# ID_PCB.net
KiCad netlist of a schematic drawn in EasyEDA Pro
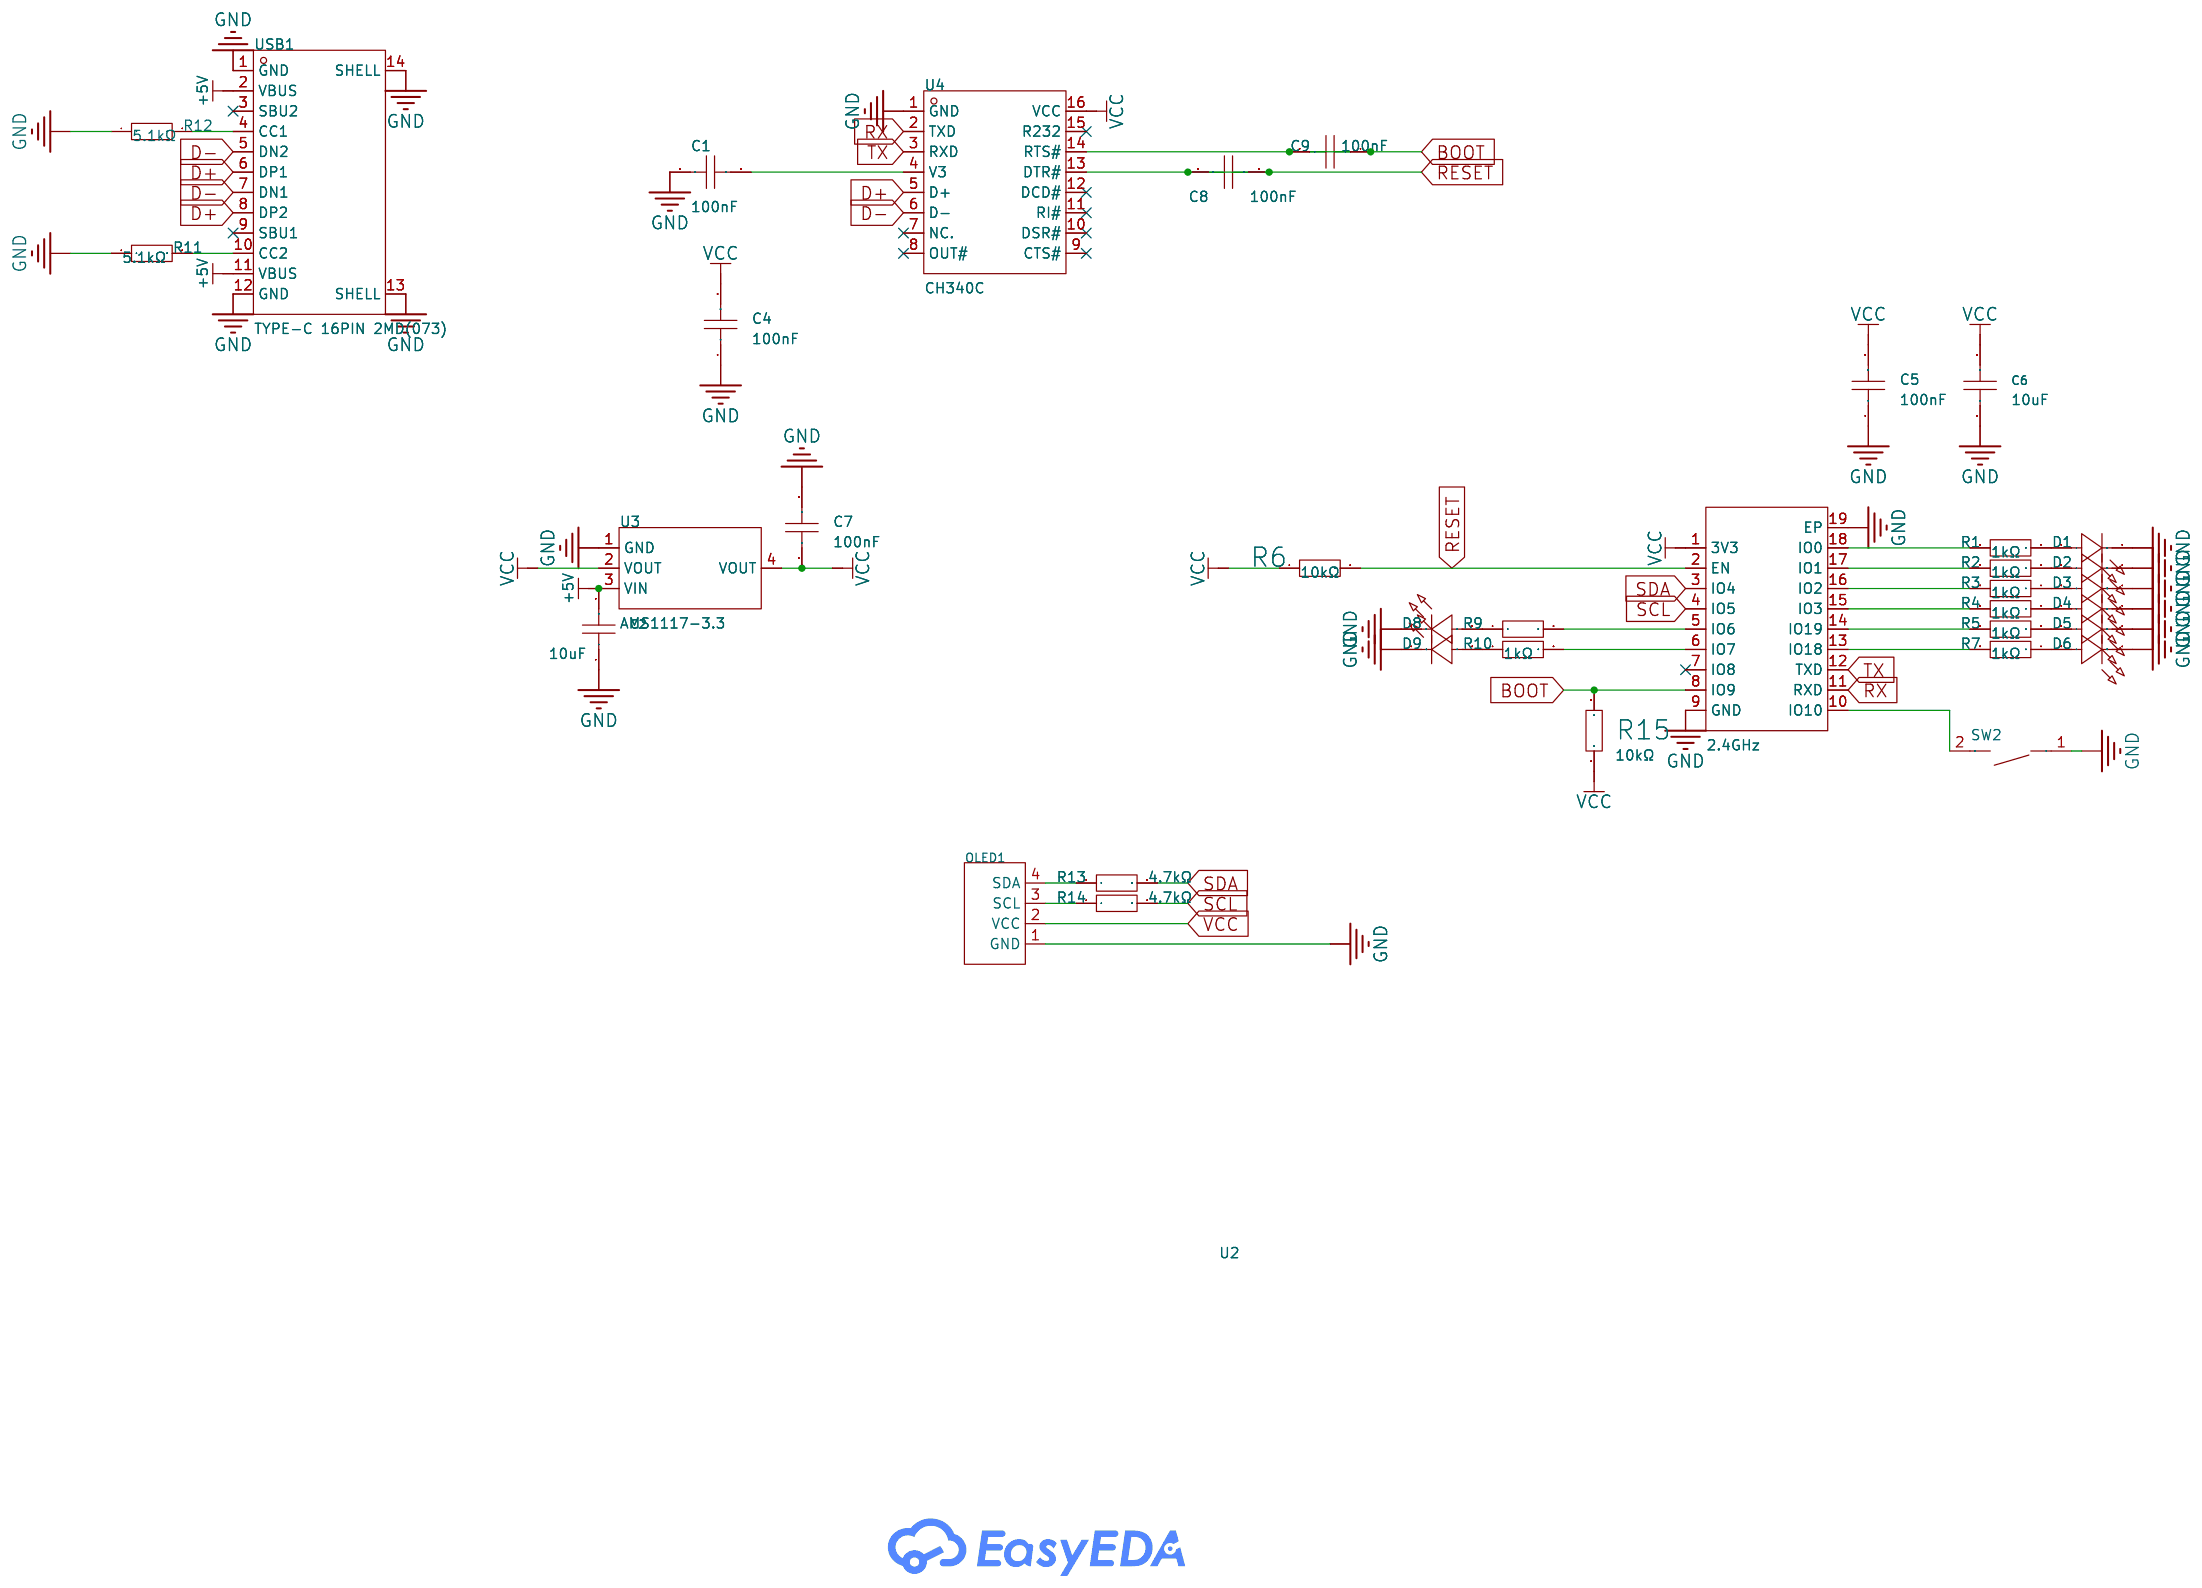
[diagram p0: schematic sheet]

(export (version "E")
  (design (tool "Eeschema 10.0.6"))
  (components
    (comp (ref "C1")
      (value "100nF")
      (footprint "easyedapro:C0603")
      (description "Capacitance:100nF Tolerance:±10% Tolerance:±10% Voltage Rating:50V Temperature Coefficient:X7R")
      (fields
        (field (name "Manufacturer Part") "CC0603KRX7R9BB104")
        (field (name "Manufacturer") "YAGEO(国巨)")
      )
      (libsource (lib "easyedapro") (part "CC0603KRX7R9BB104"))
    )
    (comp (ref "C2")
      (value "10uF")
      (footprint "easyedapro:C0603")
      (description "Capacitance:10uF Tolerance:±20% Tolerance:±20% Voltage Rating:25V Temperature Coefficient:X5R")
      (fields
        (field (name "Manufacturer Part") "CL10A106MA8NRNC")
        (field (name "Manufacturer") "SAMSUNG(三星)")
      )
      (libsource (lib "easyedapro") (part "CL10A106MA8NRNC"))
    )
    (comp (ref "C4")
      (value "100nF")
      (footprint "easyedapro:C0603")
      (description "Capacitance:100nF Tolerance:±10% Tolerance:±10% Voltage Rating:50V Temperature Coefficient:X7R")
      (fields
        (field (name "Manufacturer Part") "CC0603KRX7R9BB104")
        (field (name "Manufacturer") "YAGEO(国巨)")
      )
      (libsource (lib "easyedapro") (part "CC0603KRX7R9BB104"))
    )
    (comp (ref "C5")
      (value "100nF")
      (footprint "easyedapro:C0603")
      (description "Capacitance:100nF Tolerance:±10% Tolerance:±10% Voltage Rating:50V Temperature Coefficient:X7R")
      (fields
        (field (name "Manufacturer Part") "CC0603KRX7R9BB104")
        (field (name "Manufacturer") "YAGEO(国巨)")
      )
      (libsource (lib "easyedapro") (part "CC0603KRX7R9BB104"))
    )
    (comp (ref "C6")
      (value "10uF")
      (footprint "easyedapro:C0603")
      (description "Capacitance:10uF Tolerance:±20% Tolerance:±20% Voltage Rating:25V Temperature Coefficient:X5R")
      (fields
        (field (name "Manufacturer Part") "CL10A106MA8NRNC")
        (field (name "Manufacturer") "SAMSUNG(三星)")
      )
      (libsource (lib "easyedapro") (part "CL10A106MA8NRNC"))
    )
    (comp (ref "C7")
      (value "100nF")
      (footprint "easyedapro:C0603")
      (description "Capacitance:100nF Tolerance:±10% Tolerance:±10% Voltage Rating:50V Temperature Coefficient:X7R")
      (fields
        (field (name "Manufacturer Part") "CC0603KRX7R9BB104")
        (field (name "Manufacturer") "YAGEO(国巨)")
      )
      (libsource (lib "easyedapro") (part "CC0603KRX7R9BB104"))
    )
    (comp (ref "C8")
      (value "100nF")
      (footprint "easyedapro:C0603")
      (description "Capacitance:100nF Tolerance:±10% Tolerance:±10% Voltage Rating:50V Temperature Coefficient:X7R")
      (fields
        (field (name "Manufacturer Part") "CC0603KRX7R9BB104")
        (field (name "Manufacturer") "YAGEO(国巨)")
      )
      (libsource (lib "easyedapro") (part "CC0603KRX7R9BB104"))
    )
    (comp (ref "C9")
      (value "100nF")
      (footprint "easyedapro:C0603")
      (description "Capacitance:100nF Tolerance:±10% Tolerance:±10% Voltage Rating:50V Temperature Coefficient:X7R")
      (fields
        (field (name "Manufacturer Part") "CC0603KRX7R9BB104")
        (field (name "Manufacturer") "YAGEO(国巨)")
      )
      (libsource (lib "easyedapro") (part "CC0603KRX7R9BB104"))
    )
    (comp (ref "D1")
      (value "YLED0603Y")
      (footprint "easyedapro:LED0603-RD-1")
      (fields (field (name "Manufacturer") "YONGYUTAI(永裕泰)"))
      (libsource (lib "easyedapro") (part "YLED0603Y"))
    )
    (comp (ref "D2")
      (value "YLED0603Y")
      (footprint "easyedapro:LED0603-RD-1")
      (fields (field (name "Manufacturer") "YONGYUTAI(永裕泰)"))
      (libsource (lib "easyedapro") (part "YLED0603Y"))
    )
    (comp (ref "D3")
      (value "YLED0603Y")
      (footprint "easyedapro:LED0603-RD-1")
      (fields (field (name "Manufacturer") "YONGYUTAI(永裕泰)"))
      (libsource (lib "easyedapro") (part "YLED0603Y"))
    )
    (comp (ref "D4")
      (value "YLED0603Y")
      (footprint "easyedapro:LED0603-RD-1")
      (fields (field (name "Manufacturer") "YONGYUTAI(永裕泰)"))
      (libsource (lib "easyedapro") (part "YLED0603Y"))
    )
    (comp (ref "D5")
      (value "YLED0603Y")
      (footprint "easyedapro:LED0603-RD-1")
      (fields (field (name "Manufacturer") "YONGYUTAI(永裕泰)"))
      (libsource (lib "easyedapro") (part "YLED0603Y"))
    )
    (comp (ref "D6")
      (value "YLED0603Y")
      (footprint "easyedapro:LED0603-RD-1")
      (fields (field (name "Manufacturer") "YONGYUTAI(永裕泰)"))
      (libsource (lib "easyedapro") (part "YLED0603Y"))
    )
    (comp (ref "D8")
      (value "YLED0603Y")
      (footprint "easyedapro:LED0603-RD-1")
      (fields (field (name "Manufacturer") "YONGYUTAI(永裕泰)"))
      (libsource (lib "easyedapro") (part "YLED0603Y"))
    )
    (comp (ref "D9")
      (value "YLED0603Y")
      (footprint "easyedapro:LED0603-RD-1")
      (fields (field (name "Manufacturer") "YONGYUTAI(永裕泰)"))
      (libsource (lib "easyedapro") (part "YLED0603Y"))
    )
    (comp (ref "OLED1")
      (value "HS91L02W2C01")
      (footprint "easyedapro:OLED-TH_L38.0-W12.0_HS91L02W2C01")
      (fields (field (name "Manufacturer") "HS(汉昇)"))
      (libsource (lib "easyedapro") (part "HS91L02W2C01"))
    )
    (comp (ref "R1")
      (value "1kΩ")
      (footprint "easyedapro:R0603")
      (fields
        (field (name "Manufacturer Part") "0603WAF1001T5E")
        (field (name "Manufacturer") "UNI-ROYAL(厚声)")
      )
      (libsource (lib "easyedapro") (part "0603WAF1001T5E"))
    )
    (comp (ref "R2")
      (value "1kΩ")
      (footprint "easyedapro:R0603")
      (fields
        (field (name "Manufacturer Part") "0603WAF1001T5E")
        (field (name "Manufacturer") "UNI-ROYAL(厚声)")
      )
      (libsource (lib "easyedapro") (part "0603WAF1001T5E"))
    )
    (comp (ref "R3")
      (value "1kΩ")
      (footprint "easyedapro:R0603")
      (fields
        (field (name "Manufacturer Part") "0603WAF1001T5E")
        (field (name "Manufacturer") "UNI-ROYAL(厚声)")
      )
      (libsource (lib "easyedapro") (part "0603WAF1001T5E"))
    )
    (comp (ref "R4")
      (value "1kΩ")
      (footprint "easyedapro:R0603")
      (fields
        (field (name "Manufacturer Part") "0603WAF1001T5E")
        (field (name "Manufacturer") "UNI-ROYAL(厚声)")
      )
      (libsource (lib "easyedapro") (part "0603WAF1001T5E"))
    )
    (comp (ref "R5")
      (value "1kΩ")
      (footprint "easyedapro:R0603")
      (fields
        (field (name "Manufacturer Part") "0603WAF1001T5E")
        (field (name "Manufacturer") "UNI-ROYAL(厚声)")
      )
      (libsource (lib "easyedapro") (part "0603WAF1001T5E"))
    )
    (comp (ref "R6")
      (value "10kΩ")
      (footprint "easyedapro:R0603")
      (fields
        (field (name "Manufacturer Part") "0603WAF1002T5E")
        (field (name "Manufacturer") "UNI-ROYAL(厚声)")
      )
      (libsource (lib "easyedapro") (part "0603WAF1002T5E"))
    )
    (comp (ref "R7")
      (value "1kΩ")
      (footprint "easyedapro:R0603")
      (fields
        (field (name "Manufacturer Part") "0603WAF1001T5E")
        (field (name "Manufacturer") "UNI-ROYAL(厚声)")
      )
      (libsource (lib "easyedapro") (part "0603WAF1001T5E"))
    )
    (comp (ref "R9")
      (value "1kΩ")
      (footprint "easyedapro:R0603")
      (fields
        (field (name "Manufacturer Part") "0603WAF1001T5E")
        (field (name "Manufacturer") "UNI-ROYAL(厚声)")
      )
      (libsource (lib "easyedapro") (part "0603WAF1001T5E"))
    )
    (comp (ref "R10")
      (value "1kΩ")
      (footprint "easyedapro:R0603")
      (fields
        (field (name "Manufacturer Part") "0603WAF1001T5E")
        (field (name "Manufacturer") "UNI-ROYAL(厚声)")
      )
      (libsource (lib "easyedapro") (part "0603WAF1001T5E"))
    )
    (comp (ref "R11")
      (value "5.1kΩ")
      (footprint "easyedapro:R0603")
      (fields
        (field (name "Manufacturer Part") "0603WAF5101T5E")
        (field (name "Manufacturer") "UNI-ROYAL(厚声)")
      )
      (libsource (lib "easyedapro") (part "0603WAF5101T5E"))
    )
    (comp (ref "R12")
      (value "5.1kΩ")
      (footprint "easyedapro:R0603")
      (fields
        (field (name "Manufacturer Part") "0603WAF5101T5E")
        (field (name "Manufacturer") "UNI-ROYAL(厚声)")
      )
      (libsource (lib "easyedapro") (part "0603WAF5101T5E"))
    )
    (comp (ref "R13")
      (value "4.7kΩ")
      (footprint "easyedapro:R0603")
      (fields (field (name "Manufacturer Part") "RC0603FR-074K7L") (field (name "Manufacturer") "YAGEO(国巨)"))
      (libsource (lib "easyedapro") (part "RC0603FR-074K7L"))
    )
    (comp (ref "R14")
      (value "4.7kΩ")
      (footprint "easyedapro:R0603")
      (fields (field (name "Manufacturer Part") "RC0603FR-074K7L") (field (name "Manufacturer") "YAGEO(国巨)"))
      (libsource (lib "easyedapro") (part "RC0603FR-074K7L"))
    )
    (comp (ref "R15")
      (value "10kΩ")
      (footprint "easyedapro:R0603")
      (fields
        (field (name "Manufacturer Part") "0603WAF1002T5E")
        (field (name "Manufacturer") "UNI-ROYAL(厚声)")
      )
      (libsource (lib "easyedapro") (part "0603WAF1002T5E"))
    )
    (comp (ref "SW2")
      (value "TS-1088-AR02016")
      (footprint "easyedapro:SW-SMD_L3.9-W3.0-P4.45")
      (fields (field (name "Manufacturer") "XUNPU(讯普)"))
      (libsource (lib "easyedapro") (part "TS-1088-AR02016"))
    )
    (comp (ref "U2")
      (value "2.4GHz")
      (footprint "easyedapro:BULETM-SMD_ESPRESSIF_ESP32-C3-WROOM-02-N4-4MB")
      (fields
        (field (name "Manufacturer Part") "ESP32-C3-WROOM-02-N4")
        (field (name "Manufacturer") "ESPRESSIF(乐鑫)")
      )
      (libsource (lib "easyedapro") (part "ESP32-C3-WROOM-02-N4(4MB)"))
    )
    (comp (ref "U3")
      (value "AMS1117-3.3")
      (footprint "easyedapro:SOT-223-3_L6.5-W3.4-P2.30-LS7.0-BR")
      (fields (field (name "Manufacturer") "AMS"))
      (libsource (lib "easyedapro") (part "AMS1117-3.3"))
    )
    (comp (ref "U4")
      (value "CH340C")
      (footprint "easyedapro:SOP-16_L10.0-W3.9-P1.27-LS6.0-BL")
      (fields (field (name "Manufacturer") "WCH(南京沁恒)"))
      (libsource (lib "easyedapro") (part "CH340C"))
    )
    (comp (ref "USB1")
      (value "TYPE-C 16PIN 2MD(073)")
      (footprint "easyedapro:USB-C-SMD_TYPE-C-6PIN-2MD-073")
      (fields (field (name "Manufacturer") "SHOU HAN(首韩)"))
      (libsource (lib "easyedapro") (part "TYPE-C 16PIN 2MD(073)"))
    )
  )
  (nets
    (net (code "1") (name "+5V") (class "Default")
      (node (ref "C2") (pin "2") (pinfunction "2_2") (pintype "input"))
      (node (ref "U3") (pin "3") (pinfunction "VIN_3") (pintype "unspecified"))
      (node (ref "USB1") (pin "11") (pinfunction "VBUS_11") (pintype "unspecified"))
      (node (ref "USB1") (pin "2") (pinfunction "VBUS_2") (pintype "unspecified"))
    )
    (net (code "2") (name "BOOT") (class "Default")
      (node (ref "C9") (pin "1") (pinfunction "1_1") (pintype "unspecified"))
      (node (ref "C9") (pin "2") (pinfunction "2_2") (pintype "unspecified"))
      (node (ref "R15") (pin "2") (pinfunction "2_2") (pintype "input"))
      (node (ref "U2") (pin "8") (pinfunction "IO9_8") (pintype "unspecified"))
      (node (ref "U4") (pin "14") (pinfunction "RTS#_14") (pintype "unspecified"))
    )
    (net (code "3") (name "D+") (class "Default")
      (node (ref "U4") (pin "5") (pinfunction "D+_5") (pintype "unspecified"))
      (node (ref "USB1") (pin "6") (pinfunction "DP1_6") (pintype "unspecified"))
      (node (ref "USB1") (pin "8") (pinfunction "DP2_8") (pintype "unspecified"))
    )
    (net (code "4") (name "D-") (class "Default")
      (node (ref "U4") (pin "6") (pinfunction "D-_6") (pintype "unspecified"))
      (node (ref "USB1") (pin "5") (pinfunction "DN2_5") (pintype "unspecified"))
      (node (ref "USB1") (pin "7") (pinfunction "DN1_7") (pintype "unspecified"))
    )
    (net (code "5") (name "GND") (class "Default")
      (node (ref "C1") (pin "1") (pinfunction "1_1") (pintype "unspecified"))
      (node (ref "C2") (pin "1") (pinfunction "1_1") (pintype "input"))
      (node (ref "C4") (pin "1") (pinfunction "1_1") (pintype "unspecified"))
      (node (ref "C5") (pin "1") (pinfunction "1_1") (pintype "unspecified"))
      (node (ref "C6") (pin "1") (pinfunction "1_1") (pintype "input"))
      (node (ref "C7") (pin "2") (pinfunction "2_2") (pintype "unspecified"))
      (node (ref "D1") (pin "1") (pinfunction "C_1") (pintype "unspecified"))
      (node (ref "D2") (pin "1") (pinfunction "C_1") (pintype "unspecified"))
      (node (ref "D3") (pin "1") (pinfunction "C_1") (pintype "unspecified"))
      (node (ref "D4") (pin "1") (pinfunction "C_1") (pintype "unspecified"))
      (node (ref "D5") (pin "1") (pinfunction "C_1") (pintype "unspecified"))
      (node (ref "D6") (pin "1") (pinfunction "C_1") (pintype "unspecified"))
      (node (ref "D8") (pin "1") (pinfunction "C_1") (pintype "unspecified"))
      (node (ref "D9") (pin "1") (pinfunction "C_1") (pintype "unspecified"))
      (node (ref "OLED1") (pin "1") (pinfunction "GND_1") (pintype "input"))
      (node (ref "R11") (pin "1") (pinfunction "1_1") (pintype "input"))
      (node (ref "R12") (pin "1") (pinfunction "1_1") (pintype "input"))
      (node (ref "SW2") (pin "1") (pinfunction "1_1") (pintype "unspecified"))
      (node (ref "U2") (pin "19") (pinfunction "EP_19") (pintype "unspecified"))
      (node (ref "U2") (pin "9") (pinfunction "GND_9") (pintype "unspecified"))
      (node (ref "U3") (pin "1") (pinfunction "GND_1") (pintype "unspecified"))
      (node (ref "U4") (pin "1") (pinfunction "GND_1") (pintype "unspecified"))
      (node (ref "USB1") (pin "1") (pinfunction "GND_1") (pintype "unspecified"))
      (node (ref "USB1") (pin "12") (pinfunction "GND_12") (pintype "unspecified"))
      (node (ref "USB1") (pin "13") (pinfunction "SHELL_13") (pintype "unspecified"))
      (node (ref "USB1") (pin "14") (pinfunction "SHELL_14") (pintype "unspecified"))
    )
    (net (code "6") (name "Net-(D1-A)") (class "Default")
      (node (ref "D1") (pin "2") (pinfunction "A_2") (pintype "unspecified"))
      (node (ref "R1") (pin "1") (pinfunction "1_1") (pintype "input"))
    )
    (net (code "7") (name "Net-(D2-A)") (class "Default")
      (node (ref "D2") (pin "2") (pinfunction "A_2") (pintype "unspecified"))
      (node (ref "R2") (pin "1") (pinfunction "1_1") (pintype "input"))
    )
    (net (code "8") (name "Net-(D3-A)") (class "Default")
      (node (ref "D3") (pin "2") (pinfunction "A_2") (pintype "unspecified"))
      (node (ref "R3") (pin "1") (pinfunction "1_1") (pintype "input"))
    )
    (net (code "9") (name "Net-(D4-A)") (class "Default")
      (node (ref "D4") (pin "2") (pinfunction "A_2") (pintype "unspecified"))
      (node (ref "R4") (pin "1") (pinfunction "1_1") (pintype "input"))
    )
    (net (code "10") (name "Net-(D5-A)") (class "Default")
      (node (ref "D5") (pin "2") (pinfunction "A_2") (pintype "unspecified"))
      (node (ref "R5") (pin "1") (pinfunction "1_1") (pintype "input"))
    )
    (net (code "11") (name "Net-(D6-A)") (class "Default")
      (node (ref "D6") (pin "2") (pinfunction "A_2") (pintype "unspecified"))
      (node (ref "R7") (pin "1") (pinfunction "1_1") (pintype "input"))
    )
    (net (code "12") (name "Net-(D8-A)") (class "Default")
      (node (ref "D8") (pin "2") (pinfunction "A_2") (pintype "unspecified"))
      (node (ref "R9") (pin "1") (pinfunction "1_1") (pintype "input"))
    )
    (net (code "13") (name "Net-(D9-A)") (class "Default")
      (node (ref "D9") (pin "2") (pinfunction "A_2") (pintype "unspecified"))
      (node (ref "R10") (pin "1") (pinfunction "1_1") (pintype "input"))
    )
    (net (code "14") (name "Net-(OLED1-SCL)") (class "Default")
      (node (ref "OLED1") (pin "3") (pinfunction "SCL_3") (pintype "input"))
      (node (ref "R14") (pin "1") (pinfunction "1_1") (pintype "input"))
    )
    (net (code "15") (name "Net-(OLED1-SDA)") (class "Default")
      (node (ref "OLED1") (pin "4") (pinfunction "SDA_4") (pintype "input"))
      (node (ref "R13") (pin "1") (pinfunction "1_1") (pintype "input"))
    )
    (net (code "16") (name "Net-(U2-IO0)") (class "Default")
      (node (ref "R1") (pin "2") (pinfunction "2_2") (pintype "input"))
      (node (ref "U2") (pin "18") (pinfunction "IO0_18") (pintype "unspecified"))
    )
    (net (code "17") (name "Net-(U2-IO1)") (class "Default")
      (node (ref "R2") (pin "2") (pinfunction "2_2") (pintype "input"))
      (node (ref "U2") (pin "17") (pinfunction "IO1_17") (pintype "unspecified"))
    )
    (net (code "18") (name "Net-(U2-IO2)") (class "Default")
      (node (ref "R3") (pin "2") (pinfunction "2_2") (pintype "input"))
      (node (ref "U2") (pin "16") (pinfunction "IO2_16") (pintype "unspecified"))
    )
    (net (code "19") (name "Net-(U2-IO3)") (class "Default")
      (node (ref "R4") (pin "2") (pinfunction "2_2") (pintype "input"))
      (node (ref "U2") (pin "15") (pinfunction "IO3_15") (pintype "unspecified"))
    )
    (net (code "20") (name "Net-(U2-IO6)") (class "Default")
      (node (ref "R9") (pin "2") (pinfunction "2_2") (pintype "input"))
      (node (ref "U2") (pin "5") (pinfunction "IO6_5") (pintype "unspecified"))
    )
    (net (code "21") (name "Net-(U2-IO7)") (class "Default")
      (node (ref "R10") (pin "2") (pinfunction "2_2") (pintype "input"))
      (node (ref "U2") (pin "6") (pinfunction "IO7_6") (pintype "unspecified"))
    )
    (net (code "22") (name "Net-(U2-IO10)") (class "Default")
      (node (ref "SW2") (pin "2") (pinfunction "2_2") (pintype "unspecified"))
      (node (ref "U2") (pin "10") (pinfunction "IO10_10") (pintype "unspecified"))
    )
    (net (code "23") (name "Net-(U2-IO18)") (class "Default")
      (node (ref "R7") (pin "2") (pinfunction "2_2") (pintype "input"))
      (node (ref "U2") (pin "13") (pinfunction "IO18_13") (pintype "unspecified"))
    )
    (net (code "24") (name "Net-(U2-IO19)") (class "Default")
      (node (ref "R5") (pin "2") (pinfunction "2_2") (pintype "input"))
      (node (ref "U2") (pin "14") (pinfunction "IO19_14") (pintype "unspecified"))
    )
    (net (code "25") (name "Net-(U4-V3)") (class "Default")
      (node (ref "C1") (pin "2") (pinfunction "2_2") (pintype "unspecified"))
      (node (ref "U4") (pin "4") (pinfunction "V3_4") (pintype "unspecified"))
    )
    (net (code "26") (name "Net-(USB1-CC1)") (class "Default")
      (node (ref "R12") (pin "2") (pinfunction "2_2") (pintype "input"))
      (node (ref "USB1") (pin "4") (pinfunction "CC1_4") (pintype "unspecified"))
    )
    (net (code "27") (name "Net-(USB1-CC2)") (class "Default")
      (node (ref "R11") (pin "2") (pinfunction "2_2") (pintype "input"))
      (node (ref "USB1") (pin "10") (pinfunction "CC2_10") (pintype "unspecified"))
    )
    (net (code "28") (name "RESET") (class "Default")
      (node (ref "C8") (pin "1") (pinfunction "1_1") (pintype "unspecified"))
      (node (ref "C8") (pin "2") (pinfunction "2_2") (pintype "unspecified"))
      (node (ref "R6") (pin "2") (pinfunction "2_2") (pintype "input"))
      (node (ref "U2") (pin "2") (pinfunction "EN_2") (pintype "unspecified"))
      (node (ref "U4") (pin "13") (pinfunction "DTR#_13") (pintype "unspecified"))
    )
    (net (code "29") (name "RX") (class "Default")
      (node (ref "U2") (pin "11") (pinfunction "RXD_11") (pintype "unspecified"))
      (node (ref "U4") (pin "2") (pinfunction "TXD_2") (pintype "unspecified"))
    )
    (net (code "30") (name "SCL") (class "Default")
      (node (ref "R14") (pin "2") (pinfunction "2_2") (pintype "input"))
      (node (ref "U2") (pin "4") (pinfunction "IO5_4") (pintype "unspecified"))
    )
    (net (code "31") (name "SDA") (class "Default")
      (node (ref "R13") (pin "2") (pinfunction "2_2") (pintype "input"))
      (node (ref "U2") (pin "3") (pinfunction "IO4_3") (pintype "unspecified"))
    )
    (net (code "32") (name "TX") (class "Default")
      (node (ref "U2") (pin "12") (pinfunction "TXD_12") (pintype "unspecified"))
      (node (ref "U4") (pin "3") (pinfunction "RXD_3") (pintype "unspecified"))
    )
    (net (code "33") (name "VCC") (class "Default")
      (node (ref "C4") (pin "2") (pinfunction "2_2") (pintype "unspecified"))
      (node (ref "C5") (pin "2") (pinfunction "2_2") (pintype "unspecified"))
      (node (ref "C6") (pin "2") (pinfunction "2_2") (pintype "input"))
      (node (ref "C7") (pin "1") (pinfunction "1_1") (pintype "unspecified"))
      (node (ref "OLED1") (pin "2") (pinfunction "VCC_2") (pintype "input"))
      (node (ref "R15") (pin "1") (pinfunction "1_1") (pintype "input"))
      (node (ref "R6") (pin "1") (pinfunction "1_1") (pintype "input"))
      (node (ref "U2") (pin "1") (pinfunction "3V3_1") (pintype "unspecified"))
      (node (ref "U3") (pin "2") (pinfunction "VOUT_2") (pintype "unspecified"))
      (node (ref "U3") (pin "4") (pinfunction "VOUT_4") (pintype "unspecified"))
      (node (ref "U4") (pin "16") (pinfunction "VCC_16") (pintype "unspecified"))
    )
    (net (code "34") (name "unconnected-(U2-IO8-Pad7)") (class "Default")
      (node (ref "U2") (pin "7") (pinfunction "IO8_7") (pintype "unspecified+no_connect"))
    )
    (net (code "35") (name "unconnected-(U4-CTS#-Pad9)") (class "Default")
      (node (ref "U4") (pin "9") (pinfunction "CTS#_9") (pintype "unspecified+no_connect"))
    )
    (net (code "36") (name "unconnected-(U4-DCD#-Pad12)") (class "Default")
      (node (ref "U4") (pin "12") (pinfunction "DCD#_12") (pintype "unspecified+no_connect"))
    )
    (net (code "37") (name "unconnected-(U4-DSR#-Pad10)") (class "Default")
      (node (ref "U4") (pin "10") (pinfunction "DSR#_10") (pintype "unspecified+no_connect"))
    )
    (net (code "38") (name "unconnected-(U4-NC.-Pad7)") (class "Default")
      (node (ref "U4") (pin "7") (pinfunction "NC._7") (pintype "unspecified+no_connect"))
    )
    (net (code "39") (name "unconnected-(U4-OUT#-Pad8)") (class "Default")
      (node (ref "U4") (pin "8") (pinfunction "OUT#_8") (pintype "unspecified+no_connect"))
    )
    (net (code "40") (name "unconnected-(U4-R232-Pad15)") (class "Default")
      (node (ref "U4") (pin "15") (pinfunction "R232_15") (pintype "unspecified+no_connect"))
    )
    (net (code "41") (name "unconnected-(U4-RI#-Pad11)") (class "Default")
      (node (ref "U4") (pin "11") (pinfunction "RI#_11") (pintype "unspecified+no_connect"))
    )
    (net (code "42") (name "unconnected-(USB1-SBU1-Pad9)") (class "Default")
      (node (ref "USB1") (pin "9") (pinfunction "SBU1_9") (pintype "unspecified+no_connect"))
    )
    (net (code "43") (name "unconnected-(USB1-SBU2-Pad3)") (class "Default")
      (node (ref "USB1") (pin "3") (pinfunction "SBU2_3") (pintype "unspecified+no_connect"))
    )
  )
)
